# design.net
KiCad netlist of a schematic drawn in EasyEDA Pro
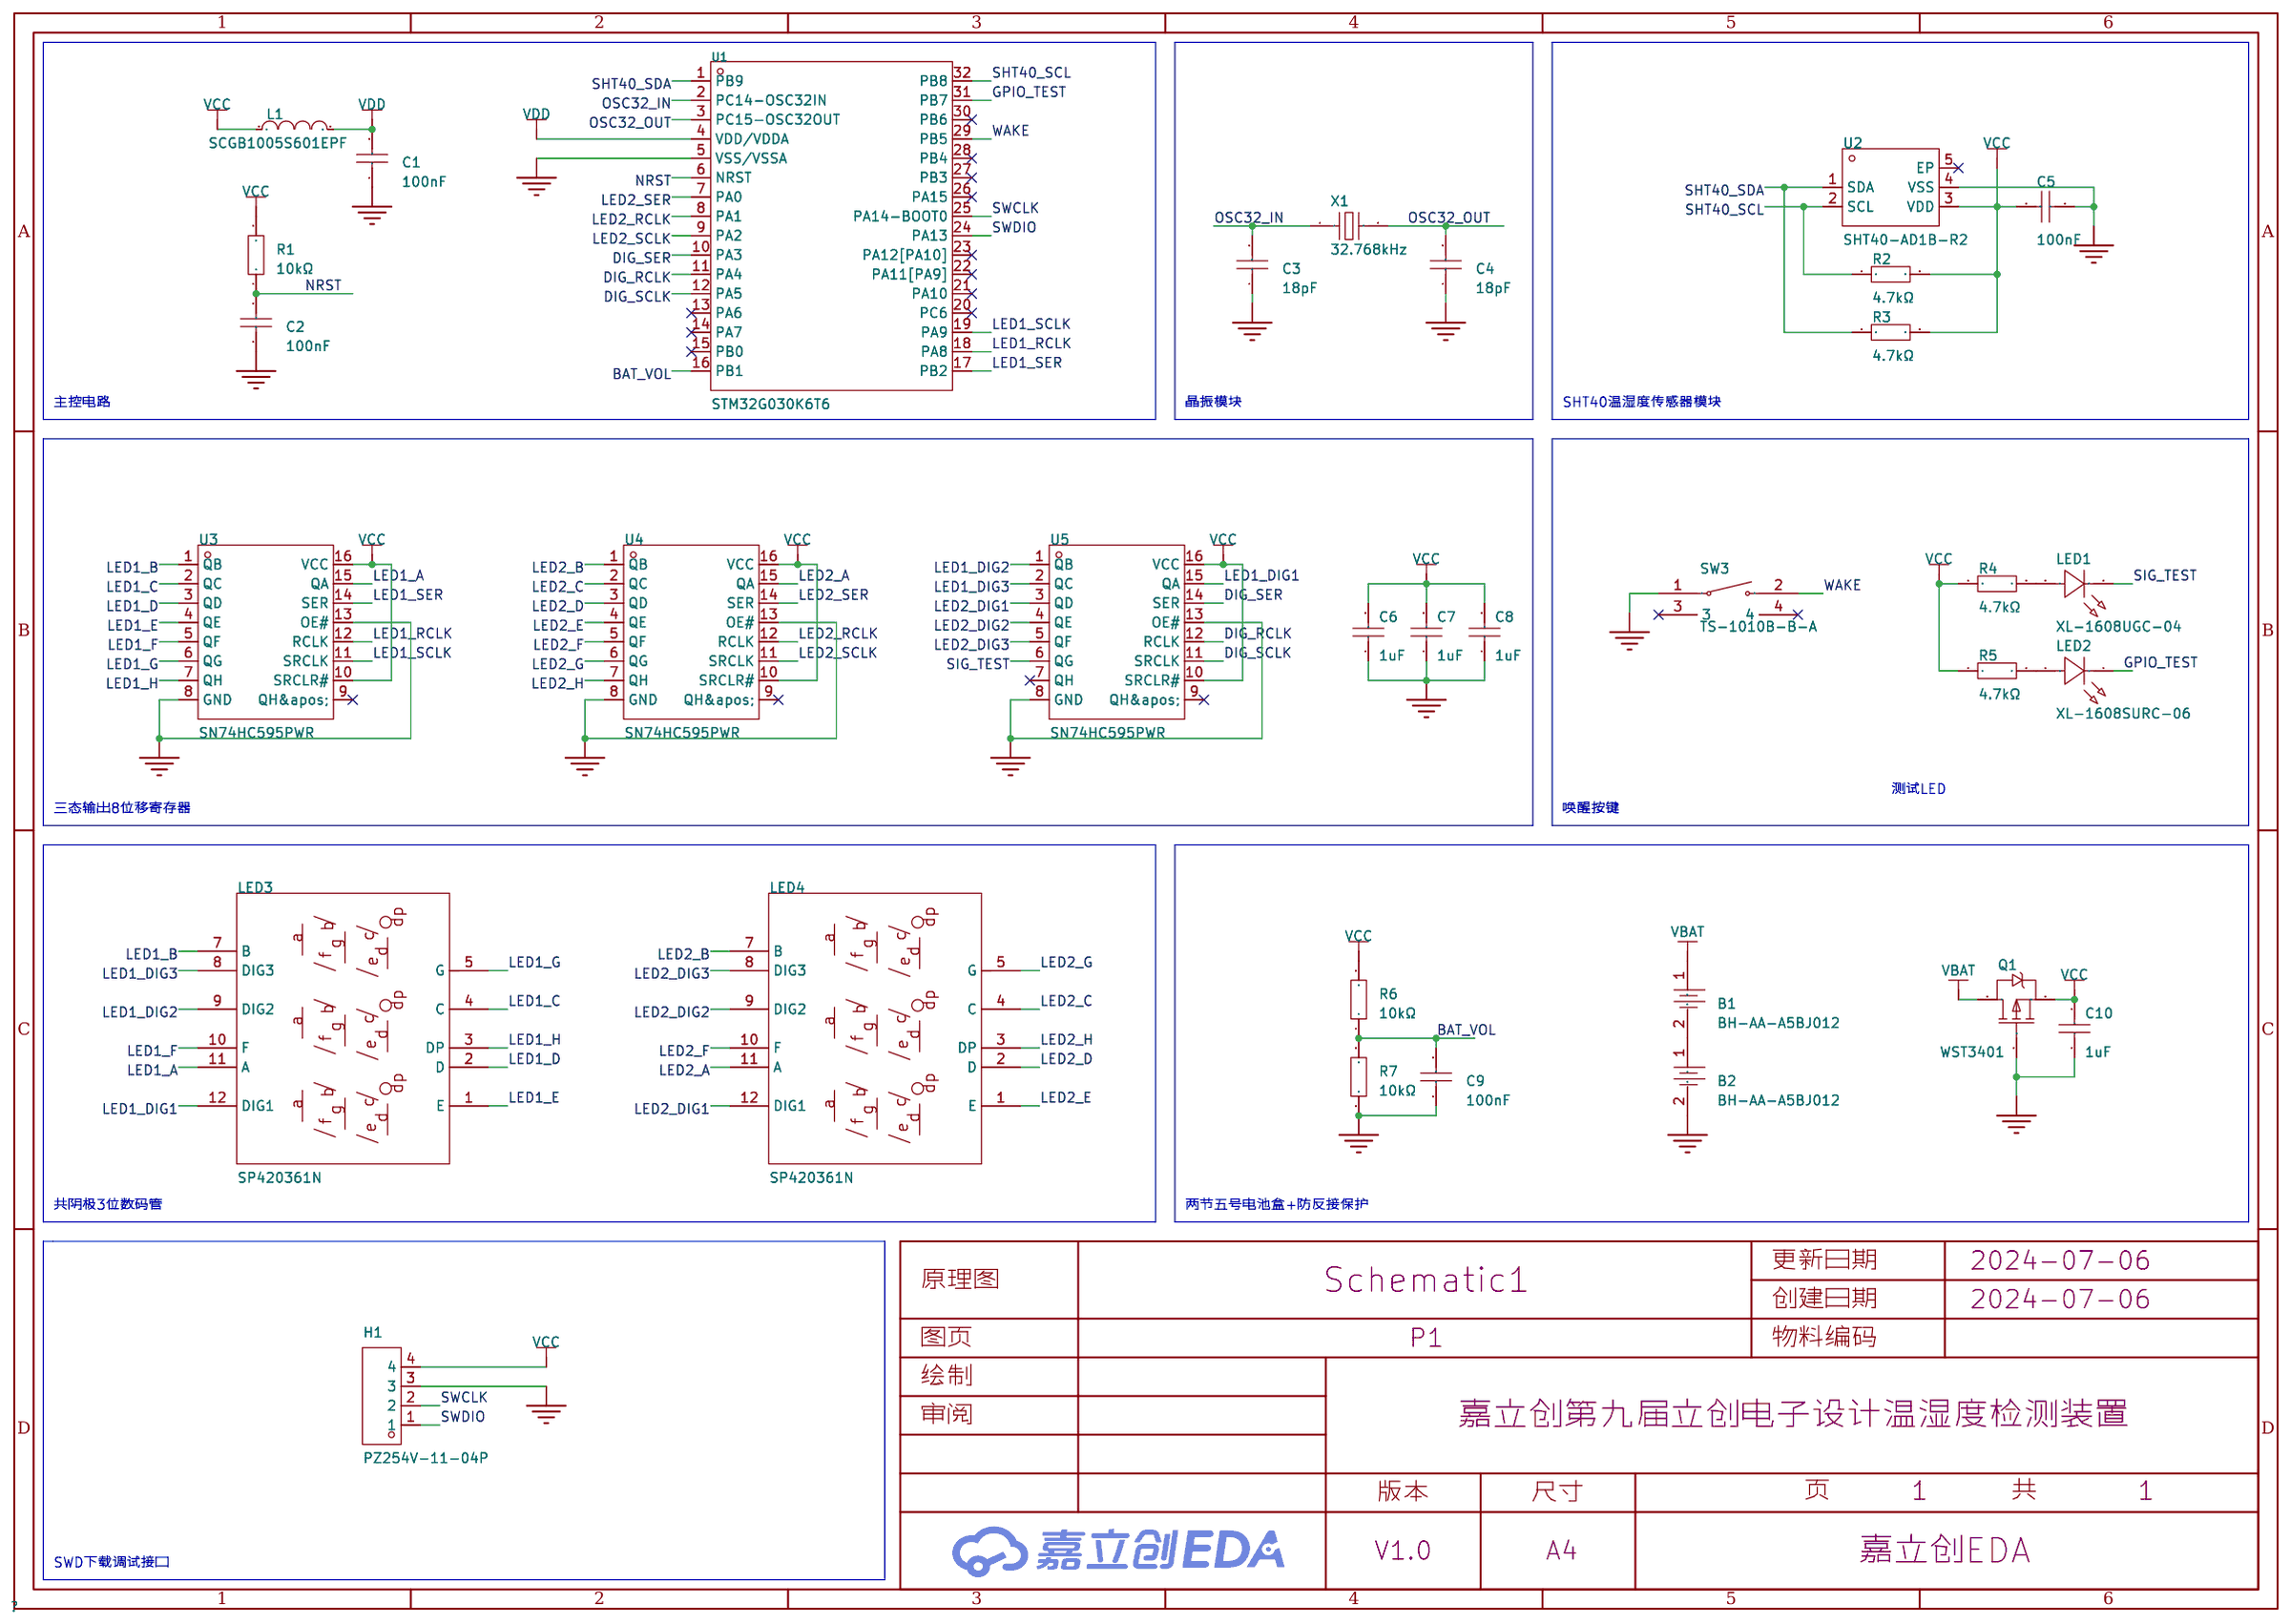
[diagram p0: schematic sheet]

(export (version "E")
  (design (tool "Eeschema 10.0.6"))
  (components
    (comp (ref "B1")
      (value "BH-AA-A5BJ012")
      (footprint "easyedapro:BAT-TH_BH-AA-A5BJ012")
      (description "连接器类型:电池盒;适用电池规格:5号;")
      (fields (field (name "Manufacturer") "MYOUNG(美阳)"))
      (libsource (lib "easyedapro") (part "BH-AA-A5BJ012"))
    )
    (comp (ref "B2")
      (value "BH-AA-A5BJ012")
      (footprint "easyedapro:BAT-TH_BH-AA-A5BJ012")
      (description "连接器类型:电池盒;适用电池规格:5号;")
      (fields (field (name "Manufacturer") "MYOUNG(美阳)"))
      (libsource (lib "easyedapro") (part "BH-AA-A5BJ012"))
    )
    (comp (ref "C1")
      (value "100nF")
      (footprint "easyedapro:C0402")
      (description "容值:100nF;精度:±10%;额定电压:25V;材质(温度系数):X7R;")
      (fields (field (name "Manufacturer Part") "0402B104K250NT") (field (name "Manufacturer") "FH(风华)"))
      (libsource (lib "easyedapro") (part "0402B104K250NT"))
    )
    (comp (ref "C2")
      (value "100nF")
      (footprint "easyedapro:C0402")
      (description "容值:100nF;精度:±10%;额定电压:25V;材质(温度系数):X7R;")
      (fields (field (name "Manufacturer Part") "0402B104K250NT") (field (name "Manufacturer") "FH(风华)"))
      (libsource (lib "easyedapro") (part "0402B104K250NT"))
    )
    (comp (ref "C3")
      (value "18pF")
      (footprint "easyedapro:C0402")
      (description "容值:18pF;精度:±5%;额定电压:50V;材质(温度系数):C0G;")
      (fields (field (name "Manufacturer Part") "0402CG180J500NT") (field (name "Manufacturer") "FH(风华)"))
      (libsource (lib "easyedapro") (part "0402CG180J500NT"))
    )
    (comp (ref "C4")
      (value "18pF")
      (footprint "easyedapro:C0402")
      (description "容值:18pF;精度:±5%;额定电压:50V;材质(温度系数):C0G;")
      (fields (field (name "Manufacturer Part") "0402CG180J500NT") (field (name "Manufacturer") "FH(风华)"))
      (libsource (lib "easyedapro") (part "0402CG180J500NT"))
    )
    (comp (ref "C5")
      (value "100nF")
      (footprint "easyedapro:C0402")
      (description "容值:100nF;精度:±10%;额定电压:25V;材质(温度系数):X7R;")
      (fields (field (name "Manufacturer Part") "0402B104K250NT") (field (name "Manufacturer") "FH(风华)"))
      (libsource (lib "easyedapro") (part "0402B104K250NT"))
    )
    (comp (ref "C6")
      (value "1uF")
      (footprint "easyedapro:C0402")
      (description "容值:1uF;精度:±10%;额定电压:6.3V;材质(温度系数):X5R;")
      (fields (field (name "Manufacturer Part") "0402X105K6R3NT") (field (name "Manufacturer") "FH(风华)"))
      (libsource (lib "easyedapro") (part "0402X105K6R3NT"))
    )
    (comp (ref "C7")
      (value "1uF")
      (footprint "easyedapro:C0402")
      (description "容值:1uF;精度:±10%;额定电压:6.3V;材质(温度系数):X5R;")
      (fields (field (name "Manufacturer Part") "0402X105K6R3NT") (field (name "Manufacturer") "FH(风华)"))
      (libsource (lib "easyedapro") (part "0402X105K6R3NT"))
    )
    (comp (ref "C8")
      (value "1uF")
      (footprint "easyedapro:C0402")
      (description "容值:1uF;精度:±10%;额定电压:6.3V;材质(温度系数):X5R;")
      (fields (field (name "Manufacturer Part") "0402X105K6R3NT") (field (name "Manufacturer") "FH(风华)"))
      (libsource (lib "easyedapro") (part "0402X105K6R3NT"))
    )
    (comp (ref "C9")
      (value "100nF")
      (footprint "easyedapro:C0402")
      (description "容值:100nF;精度:±10%;额定电压:25V;材质(温度系数):X7R;")
      (fields (field (name "Manufacturer Part") "0402B104K250NT") (field (name "Manufacturer") "FH(风华)"))
      (libsource (lib "easyedapro") (part "0402B104K250NT"))
    )
    (comp (ref "C10")
      (value "1uF")
      (footprint "easyedapro:C0402")
      (description "容值:1uF;精度:±10%;额定电压:6.3V;材质(温度系数):X5R;")
      (fields (field (name "Manufacturer Part") "0402X105K6R3NT") (field (name "Manufacturer") "FH(风华)"))
      (libsource (lib "easyedapro") (part "0402X105K6R3NT"))
    )
    (comp (ref "H1")
      (value "PZ254V-11-04P")
      (footprint "easyedapro:HDR-TH_4P-P2.54-V-M")
      (fields (field (name "Manufacturer") "XFCN(兴飞)"))
      (libsource (lib "easyedapro") (part "PZ254V-11-04P_C2691448"))
    )
    (comp (ref "L1")
      (value "SCGB1005S601EPF")
      (footprint "easyedapro:L0402")
      (description "标称阻抗@测试频率:600Ω@100MHz;直流电阻(RDC):1Ω;")
      (fields (field (name "Manufacturer") "SOCAY(硕凯)"))
      (libsource (lib "easyedapro") (part "SCGB1005S601EPF"))
    )
    (comp (ref "LED1")
      (value "XL-1608UGC-04")
      (footprint "easyedapro:LED0603-RD_GREEN")
      (fields (field (name "Manufacturer") "XINGLIGHT(成兴光)"))
      (libsource (lib "easyedapro") (part "XL-1608UGC-04"))
    )
    (comp (ref "LED2")
      (value "XL-1608SURC-06")
      (footprint "easyedapro:LED0603-RD_RED")
      (description "发光颜色:红色;功率:55mW;正向电流:25mA;主波长:617nm~621nm;透镜颜色:无色透明透镜;色温:-;发光角度:120°;载带方式:正贴;工作温度:-30°C~+85°C;")
      (fields (field (name "Manufacturer") "XINGLIGHT(成兴光)"))
      (libsource (lib "easyedapro") (part "XL-1608SURC-06"))
    )
    (comp (ref "LED3")
      (value "SP420361N")
      (footprint "easyedapro:LED-SEG-TH_SP420361N")
      (description "数码管位数:3位;发光颜色:红色;LED极性:共阴极;数字/字母大小(英寸):0.36;")
      (fields (field (name "Manufacturer") "ARKLED(方舟)"))
      (libsource (lib "easyedapro") (part "SP420361N"))
    )
    (comp (ref "LED4")
      (value "SP420361N")
      (footprint "easyedapro:LED-SEG-TH_SP420361N")
      (description "数码管位数:3位;发光颜色:红色;LED极性:共阴极;数字/字母大小(英寸):0.36;")
      (fields (field (name "Manufacturer") "ARKLED(方舟)"))
      (libsource (lib "easyedapro") (part "SP420361N"))
    )
    (comp (ref "Q1")
      (value "WST3401")
      (footprint "easyedapro:SOT-23-3_L2.9-W1.6-P1.90-LS2.8-BR")
      (fields (field (name "Manufacturer") "WINSOK(微硕)"))
      (libsource (lib "easyedapro") (part "WST3401"))
    )
    (comp (ref "R1")
      (value "10kΩ")
      (footprint "easyedapro:R0402")
      (description "电阻类型:厚膜电阻;阻值:10kΩ;精度:±1%;功率:62.5mW;最大工作电压:50V;温度系数:±100ppm/°C;")
      (fields (field (name "Manufacturer Part") "RC0402FR-0710KL") (field (name "Manufacturer") "YAGEO(国巨)"))
      (libsource (lib "easyedapro") (part "RC0402FR-0710KL"))
    )
    (comp (ref "R2")
      (value "4.7kΩ")
      (footprint "easyedapro:R0402")
      (description "电阻类型:厚膜电阻;阻值:4.7kΩ;精度:±1%;功率:62.5mW;最大工作电压:50V;温度系数:±100ppm/°C;")
      (fields (field (name "Manufacturer Part") "RC0402FR-074K7L") (field (name "Manufacturer") "YAGEO(国巨)"))
      (libsource (lib "easyedapro") (part "RC0402FR-074K7L"))
    )
    (comp (ref "R3")
      (value "4.7kΩ")
      (footprint "easyedapro:R0402")
      (description "电阻类型:厚膜电阻;阻值:4.7kΩ;精度:±1%;功率:62.5mW;最大工作电压:50V;温度系数:±100ppm/°C;")
      (fields (field (name "Manufacturer Part") "RC0402FR-074K7L") (field (name "Manufacturer") "YAGEO(国巨)"))
      (libsource (lib "easyedapro") (part "RC0402FR-074K7L"))
    )
    (comp (ref "R4")
      (value "4.7kΩ")
      (footprint "easyedapro:R0402")
      (description "电阻类型:厚膜电阻;阻值:4.7kΩ;精度:±1%;功率:62.5mW;最大工作电压:50V;温度系数:±100ppm/°C;")
      (fields (field (name "Manufacturer Part") "RC0402FR-074K7L") (field (name "Manufacturer") "YAGEO(国巨)"))
      (libsource (lib "easyedapro") (part "RC0402FR-074K7L"))
    )
    (comp (ref "R5")
      (value "4.7kΩ")
      (footprint "easyedapro:R0402")
      (description "电阻类型:厚膜电阻;阻值:4.7kΩ;精度:±1%;功率:62.5mW;最大工作电压:50V;温度系数:±100ppm/°C;")
      (fields (field (name "Manufacturer Part") "RC0402FR-074K7L") (field (name "Manufacturer") "YAGEO(国巨)"))
      (libsource (lib "easyedapro") (part "RC0402FR-074K7L"))
    )
    (comp (ref "R6")
      (value "10kΩ")
      (footprint "easyedapro:R0402")
      (description "电阻类型:厚膜电阻;阻值:10kΩ;精度:±1%;功率:62.5mW;最大工作电压:50V;温度系数:±100ppm/°C;")
      (fields (field (name "Manufacturer Part") "RC0402FR-0710KL") (field (name "Manufacturer") "YAGEO(国巨)"))
      (libsource (lib "easyedapro") (part "RC0402FR-0710KL"))
    )
    (comp (ref "R7")
      (value "10kΩ")
      (footprint "easyedapro:R0402")
      (description "电阻类型:厚膜电阻;阻值:10kΩ;精度:±1%;功率:62.5mW;最大工作电压:50V;温度系数:±100ppm/°C;")
      (fields (field (name "Manufacturer Part") "RC0402FR-0710KL") (field (name "Manufacturer") "YAGEO(国巨)"))
      (libsource (lib "easyedapro") (part "RC0402FR-0710KL"))
    )
    (comp (ref "SW3")
      (value "TS-1010B-B-A")
      (footprint "easyedapro:SW-SMD_TS-1010B-B-A")
      (fields (field (name "Manufacturer") "XKB Connectivity(中国星坤)"))
      (libsource (lib "easyedapro") (part "TS-1010B-B-A"))
    )
    (comp (ref "U1")
      (value "STM32G030K6T6")
      (footprint "easyedapro:LQFP-32_L7.0-W7.0-P0.80-LS9.0-BL")
      (description "CPU内核:CM0;程序存储容量:32KB;RAM总容量:8KB;GPIO端口数量:30;工作电压范围:2V~3.6V;CPU最大主频:64MHz;程序存储器类型:FLASH;")
      (fields (field (name "Manufacturer") "ST(意法半导体)"))
      (libsource (lib "easyedapro") (part "STM32G030K6T6"))
    )
    (comp (ref "U2")
      (value "SHT40-AD1B-R2")
      (footprint "easyedapro:DFN-4_L1.5-W1.5-P0.8-TL-EP")
      (description "±1.8% / max. ±3.5% RH 数字温湿度传感器")
      (fields (field (name "Manufacturer") "Sensirion(瑞士盛思锐)"))
      (libsource (lib "easyedapro") (part "SHT40-AD1B-R2"))
    )
    (comp (ref "U3")
      (value "SN74HC595PWR")
      (footprint "easyedapro:TSSOP-16_L5.0-W4.4-P0.65-LS6.4-BL")
      (description "功能:串行至串行或并行;电源电压:2V~6V;元件数:1;每个元件位数:8;")
      (fields (field (name "Manufacturer") "TI(德州仪器)"))
      (libsource (lib "easyedapro") (part "SN74HC595PWR"))
    )
    (comp (ref "U4")
      (value "SN74HC595PWR")
      (footprint "easyedapro:TSSOP-16_L5.0-W4.4-P0.65-LS6.4-BL")
      (description "功能:串行至串行或并行;电源电压:2V~6V;元件数:1;每个元件位数:8;")
      (fields (field (name "Manufacturer") "TI(德州仪器)"))
      (libsource (lib "easyedapro") (part "SN74HC595PWR"))
    )
    (comp (ref "U5")
      (value "SN74HC595PWR")
      (footprint "easyedapro:TSSOP-16_L5.0-W4.4-P0.65-LS6.4-BL")
      (description "功能:串行至串行或并行;电源电压:2V~6V;元件数:1;每个元件位数:8;")
      (fields (field (name "Manufacturer") "TI(德州仪器)"))
      (libsource (lib "easyedapro") (part "SN74HC595PWR"))
    )
    (comp (ref "X1")
      (value "32.768kHz")
      (footprint "easyedapro:OSC-SMD_L3.2-W1.5")
      (description "晶振类型:贴片晶振;频率:32.768kHz;常温频差:±20ppm;外接负载电容:12.5pF;频率稳定度(全温):-;")
      (fields (field (name "Manufacturer Part") "X321532768KGD2SI") (field (name "Manufacturer") "YXC(扬兴晶振)"))
      (libsource (lib "easyedapro") (part "X321532768KGD2SI"))
    )
  )
  (nets
    (net (code "1") (name "/BAT_VOL") (class "Default")
      (node (ref "C9") (pin "1") (pinfunction "1_1") (pintype "input"))
      (node (ref "R6") (pin "1") (pinfunction "1_1") (pintype "input"))
      (node (ref "R7") (pin "2") (pinfunction "2_2") (pintype "input"))
      (node (ref "U1") (pin "16") (pinfunction "PB1_16") (pintype "input"))
    )
    (net (code "2") (name "/DIG_RCLK") (class "Default")
      (node (ref "U1") (pin "11") (pinfunction "PA4_11") (pintype "input"))
      (node (ref "U5") (pin "12") (pinfunction "RCLK_12") (pintype "unspecified"))
    )
    (net (code "3") (name "/DIG_SCLK") (class "Default")
      (node (ref "U1") (pin "12") (pinfunction "PA5_12") (pintype "input"))
      (node (ref "U5") (pin "11") (pinfunction "SRCLK_11") (pintype "unspecified"))
    )
    (net (code "4") (name "/DIG_SER") (class "Default")
      (node (ref "U1") (pin "10") (pinfunction "PA3_10") (pintype "input"))
      (node (ref "U5") (pin "14") (pinfunction "SER_14") (pintype "unspecified"))
    )
    (net (code "5") (name "/GPIO_TEST") (class "Default")
      (node (ref "LED2") (pin "1") (pinfunction "K_1") (pintype "unspecified"))
      (node (ref "U1") (pin "31") (pinfunction "PB7_31") (pintype "input"))
    )
    (net (code "6") (name "/LED1_A") (class "Default")
      (node (ref "LED3") (pin "11") (pinfunction "A_11") (pintype "input"))
      (node (ref "U3") (pin "15") (pinfunction "QA_15") (pintype "unspecified"))
    )
    (net (code "7") (name "/LED1_B") (class "Default")
      (node (ref "LED3") (pin "7") (pinfunction "B_7") (pintype "input"))
      (node (ref "U3") (pin "1") (pinfunction "QB_1") (pintype "unspecified"))
    )
    (net (code "8") (name "/LED1_C") (class "Default")
      (node (ref "LED3") (pin "4") (pinfunction "C_4") (pintype "input"))
      (node (ref "U3") (pin "2") (pinfunction "QC_2") (pintype "unspecified"))
    )
    (net (code "9") (name "/LED1_D") (class "Default")
      (node (ref "LED3") (pin "2") (pinfunction "D_2") (pintype "input"))
      (node (ref "U3") (pin "3") (pinfunction "QD_3") (pintype "unspecified"))
    )
    (net (code "10") (name "/LED1_DIG1") (class "Default")
      (node (ref "LED3") (pin "12") (pinfunction "DIG1_12") (pintype "input"))
      (node (ref "U5") (pin "15") (pinfunction "QA_15") (pintype "unspecified"))
    )
    (net (code "11") (name "/LED1_DIG2") (class "Default")
      (node (ref "LED3") (pin "9") (pinfunction "DIG2_9") (pintype "input"))
      (node (ref "U5") (pin "1") (pinfunction "QB_1") (pintype "unspecified"))
    )
    (net (code "12") (name "/LED1_DIG3") (class "Default")
      (node (ref "LED3") (pin "8") (pinfunction "DIG3_8") (pintype "input"))
      (node (ref "U5") (pin "2") (pinfunction "QC_2") (pintype "unspecified"))
    )
    (net (code "13") (name "/LED1_E") (class "Default")
      (node (ref "LED3") (pin "1") (pinfunction "E_1") (pintype "input"))
      (node (ref "U3") (pin "4") (pinfunction "QE_4") (pintype "unspecified"))
    )
    (net (code "14") (name "/LED1_F") (class "Default")
      (node (ref "LED3") (pin "10") (pinfunction "F_10") (pintype "input"))
      (node (ref "U3") (pin "5") (pinfunction "QF_5") (pintype "unspecified"))
    )
    (net (code "15") (name "/LED1_G") (class "Default")
      (node (ref "LED3") (pin "5") (pinfunction "G_5") (pintype "input"))
      (node (ref "U3") (pin "6") (pinfunction "QG_6") (pintype "unspecified"))
    )
    (net (code "16") (name "/LED1_H") (class "Default")
      (node (ref "LED3") (pin "3") (pinfunction "DP_3") (pintype "input"))
      (node (ref "U3") (pin "7") (pinfunction "QH_7") (pintype "unspecified"))
    )
    (net (code "17") (name "/LED1_RCLK") (class "Default")
      (node (ref "U1") (pin "18") (pinfunction "PA8_18") (pintype "input"))
      (node (ref "U3") (pin "12") (pinfunction "RCLK_12") (pintype "unspecified"))
    )
    (net (code "18") (name "/LED1_SCLK") (class "Default")
      (node (ref "U1") (pin "19") (pinfunction "PA9_19") (pintype "input"))
      (node (ref "U3") (pin "11") (pinfunction "SRCLK_11") (pintype "unspecified"))
    )
    (net (code "19") (name "/LED1_SER") (class "Default")
      (node (ref "U1") (pin "17") (pinfunction "PB2_17") (pintype "input"))
      (node (ref "U3") (pin "14") (pinfunction "SER_14") (pintype "unspecified"))
    )
    (net (code "20") (name "/LED2_A") (class "Default")
      (node (ref "LED4") (pin "11") (pinfunction "A_11") (pintype "input"))
      (node (ref "U4") (pin "15") (pinfunction "QA_15") (pintype "unspecified"))
    )
    (net (code "21") (name "/LED2_B") (class "Default")
      (node (ref "LED4") (pin "7") (pinfunction "B_7") (pintype "input"))
      (node (ref "U4") (pin "1") (pinfunction "QB_1") (pintype "unspecified"))
    )
    (net (code "22") (name "/LED2_C") (class "Default")
      (node (ref "LED4") (pin "4") (pinfunction "C_4") (pintype "input"))
      (node (ref "U4") (pin "2") (pinfunction "QC_2") (pintype "unspecified"))
    )
    (net (code "23") (name "/LED2_D") (class "Default")
      (node (ref "LED4") (pin "2") (pinfunction "D_2") (pintype "input"))
      (node (ref "U4") (pin "3") (pinfunction "QD_3") (pintype "unspecified"))
    )
    (net (code "24") (name "/LED2_DIG1") (class "Default")
      (node (ref "LED4") (pin "12") (pinfunction "DIG1_12") (pintype "input"))
      (node (ref "U5") (pin "3") (pinfunction "QD_3") (pintype "unspecified"))
    )
    (net (code "25") (name "/LED2_DIG2") (class "Default")
      (node (ref "LED4") (pin "9") (pinfunction "DIG2_9") (pintype "input"))
      (node (ref "U5") (pin "4") (pinfunction "QE_4") (pintype "unspecified"))
    )
    (net (code "26") (name "/LED2_DIG3") (class "Default")
      (node (ref "LED4") (pin "8") (pinfunction "DIG3_8") (pintype "input"))
      (node (ref "U5") (pin "5") (pinfunction "QF_5") (pintype "unspecified"))
    )
    (net (code "27") (name "/LED2_E") (class "Default")
      (node (ref "LED4") (pin "1") (pinfunction "E_1") (pintype "input"))
      (node (ref "U4") (pin "4") (pinfunction "QE_4") (pintype "unspecified"))
    )
    (net (code "28") (name "/LED2_F") (class "Default")
      (node (ref "LED4") (pin "10") (pinfunction "F_10") (pintype "input"))
      (node (ref "U4") (pin "5") (pinfunction "QF_5") (pintype "unspecified"))
    )
    (net (code "29") (name "/LED2_G") (class "Default")
      (node (ref "LED4") (pin "5") (pinfunction "G_5") (pintype "input"))
      (node (ref "U4") (pin "6") (pinfunction "QG_6") (pintype "unspecified"))
    )
    (net (code "30") (name "/LED2_H") (class "Default")
      (node (ref "LED4") (pin "3") (pinfunction "DP_3") (pintype "input"))
      (node (ref "U4") (pin "7") (pinfunction "QH_7") (pintype "unspecified"))
    )
    (net (code "31") (name "/LED2_RCLK") (class "Default")
      (node (ref "U1") (pin "8") (pinfunction "PA1_8") (pintype "input"))
      (node (ref "U4") (pin "12") (pinfunction "RCLK_12") (pintype "unspecified"))
    )
    (net (code "32") (name "/LED2_SCLK") (class "Default")
      (node (ref "U1") (pin "9") (pinfunction "PA2_9") (pintype "input"))
      (node (ref "U4") (pin "11") (pinfunction "SRCLK_11") (pintype "unspecified"))
    )
    (net (code "33") (name "/LED2_SER") (class "Default")
      (node (ref "U1") (pin "7") (pinfunction "PA0_7") (pintype "input"))
      (node (ref "U4") (pin "14") (pinfunction "SER_14") (pintype "unspecified"))
    )
    (net (code "34") (name "/NRST") (class "Default")
      (node (ref "C2") (pin "1") (pinfunction "1_1") (pintype "input"))
      (node (ref "R1") (pin "1") (pinfunction "1_1") (pintype "input"))
      (node (ref "U1") (pin "6") (pinfunction "NRST_6") (pintype "input"))
    )
    (net (code "35") (name "/OSC32_IN") (class "Default")
      (node (ref "C3") (pin "2") (pinfunction "2_2") (pintype "input"))
      (node (ref "U1") (pin "2") (pinfunction "PC14-OSC32IN_2") (pintype "input"))
      (node (ref "X1") (pin "1") (pinfunction "1_1") (pintype "input"))
    )
    (net (code "36") (name "/OSC32_OUT") (class "Default")
      (node (ref "C4") (pin "2") (pinfunction "2_2") (pintype "input"))
      (node (ref "U1") (pin "3") (pinfunction "PC15-OSC32OUT_3") (pintype "input"))
      (node (ref "X1") (pin "2") (pinfunction "2_2") (pintype "input"))
    )
    (net (code "37") (name "/SHT40_SCL") (class "Default")
      (node (ref "R2") (pin "1") (pinfunction "1_1") (pintype "input"))
      (node (ref "U1") (pin "32") (pinfunction "PB8_32") (pintype "input"))
      (node (ref "U2") (pin "2") (pinfunction "SCL_2") (pintype "unspecified"))
    )
    (net (code "38") (name "/SHT40_SDA") (class "Default")
      (node (ref "R3") (pin "1") (pinfunction "1_1") (pintype "input"))
      (node (ref "U1") (pin "1") (pinfunction "PB9_1") (pintype "input"))
      (node (ref "U2") (pin "1") (pinfunction "SDA_1") (pintype "unspecified"))
    )
    (net (code "39") (name "/SIG_TEST") (class "Default")
      (node (ref "LED1") (pin "1") (pinfunction "K_1") (pintype "unspecified"))
      (node (ref "U5") (pin "6") (pinfunction "QG_6") (pintype "unspecified"))
    )
    (net (code "40") (name "/SWCLK") (class "Default")
      (node (ref "H1") (pin "2") (pinfunction "2_2") (pintype "unspecified"))
      (node (ref "U1") (pin "25") (pinfunction "PA14-BOOT0_25") (pintype "input"))
    )
    (net (code "41") (name "/SWDIO") (class "Default")
      (node (ref "H1") (pin "1") (pinfunction "1_1") (pintype "unspecified"))
      (node (ref "U1") (pin "24") (pinfunction "PA13_24") (pintype "input"))
    )
    (net (code "42") (name "/WAKE") (class "Default")
      (node (ref "SW3") (pin "2") (pinfunction "2_2") (pintype "input"))
      (node (ref "U1") (pin "29") (pinfunction "PB5_29") (pintype "input"))
    )
    (net (code "43") (name "GND") (class "Default")
      (node (ref "B2") (pin "2") (pinfunction "2_2") (pintype "input"))
      (node (ref "C1") (pin "2") (pinfunction "2_2") (pintype "input"))
      (node (ref "C10") (pin "1") (pinfunction "1_1") (pintype "input"))
      (node (ref "C2") (pin "2") (pinfunction "2_2") (pintype "input"))
      (node (ref "C3") (pin "1") (pinfunction "1_1") (pintype "input"))
      (node (ref "C4") (pin "1") (pinfunction "1_1") (pintype "input"))
      (node (ref "C5") (pin "2") (pinfunction "2_2") (pintype "input"))
      (node (ref "C6") (pin "1") (pinfunction "1_1") (pintype "input"))
      (node (ref "C7") (pin "1") (pinfunction "1_1") (pintype "input"))
      (node (ref "C8") (pin "1") (pinfunction "1_1") (pintype "input"))
      (node (ref "C9") (pin "2") (pinfunction "2_2") (pintype "input"))
      (node (ref "H1") (pin "3") (pinfunction "3_3") (pintype "unspecified"))
      (node (ref "Q1") (pin "1") (pinfunction "G_1") (pintype "unspecified"))
      (node (ref "R7") (pin "1") (pinfunction "1_1") (pintype "input"))
      (node (ref "SW3") (pin "1") (pinfunction "1_1") (pintype "input"))
      (node (ref "U1") (pin "5") (pinfunction "VSS/VSSA_5") (pintype "input"))
      (node (ref "U2") (pin "4") (pinfunction "VSS_4") (pintype "unspecified"))
      (node (ref "U3") (pin "13") (pinfunction "OE#_13") (pintype "unspecified"))
      (node (ref "U3") (pin "8") (pinfunction "GND_8") (pintype "unspecified"))
      (node (ref "U4") (pin "13") (pinfunction "OE#_13") (pintype "unspecified"))
      (node (ref "U4") (pin "8") (pinfunction "GND_8") (pintype "unspecified"))
      (node (ref "U5") (pin "13") (pinfunction "OE#_13") (pintype "unspecified"))
      (node (ref "U5") (pin "8") (pinfunction "GND_8") (pintype "unspecified"))
    )
    (net (code "44") (name "Net-(B1-Pad2)") (class "Default")
      (node (ref "B1") (pin "2") (pinfunction "2_2") (pintype "input"))
      (node (ref "B2") (pin "1") (pinfunction "1_1") (pintype "input"))
    )
    (net (code "45") (name "Net-(LED1-A)") (class "Default")
      (node (ref "LED1") (pin "2") (pinfunction "A_2") (pintype "unspecified"))
      (node (ref "R4") (pin "2") (pinfunction "2_2") (pintype "input"))
    )
    (net (code "46") (name "Net-(LED2-A)") (class "Default")
      (node (ref "LED2") (pin "2") (pinfunction "A_2") (pintype "unspecified"))
      (node (ref "R5") (pin "2") (pinfunction "2_2") (pintype "input"))
    )
    (net (code "47") (name "VBAT") (class "Default")
      (node (ref "B1") (pin "1") (pinfunction "1_1") (pintype "input"))
      (node (ref "Q1") (pin "3") (pinfunction "D_3") (pintype "unspecified"))
    )
    (net (code "48") (name "VCC") (class "Default")
      (node (ref "C10") (pin "2") (pinfunction "2_2") (pintype "input"))
      (node (ref "C5") (pin "1") (pinfunction "1_1") (pintype "input"))
      (node (ref "C6") (pin "2") (pinfunction "2_2") (pintype "input"))
      (node (ref "C7") (pin "2") (pinfunction "2_2") (pintype "input"))
      (node (ref "C8") (pin "2") (pinfunction "2_2") (pintype "input"))
      (node (ref "H1") (pin "4") (pinfunction "4_4") (pintype "unspecified"))
      (node (ref "L1") (pin "1") (pinfunction "1_1") (pintype "unspecified"))
      (node (ref "Q1") (pin "2") (pinfunction "S_2") (pintype "unspecified"))
      (node (ref "R1") (pin "2") (pinfunction "2_2") (pintype "input"))
      (node (ref "R2") (pin "2") (pinfunction "2_2") (pintype "input"))
      (node (ref "R3") (pin "2") (pinfunction "2_2") (pintype "input"))
      (node (ref "R4") (pin "1") (pinfunction "1_1") (pintype "input"))
      (node (ref "R5") (pin "1") (pinfunction "1_1") (pintype "input"))
      (node (ref "R6") (pin "2") (pinfunction "2_2") (pintype "input"))
      (node (ref "U2") (pin "3") (pinfunction "VDD_3") (pintype "unspecified"))
      (node (ref "U3") (pin "10") (pinfunction "SRCLR#_10") (pintype "unspecified"))
      (node (ref "U3") (pin "16") (pinfunction "VCC_16") (pintype "unspecified"))
      (node (ref "U4") (pin "10") (pinfunction "SRCLR#_10") (pintype "unspecified"))
      (node (ref "U4") (pin "16") (pinfunction "VCC_16") (pintype "unspecified"))
      (node (ref "U5") (pin "10") (pinfunction "SRCLR#_10") (pintype "unspecified"))
      (node (ref "U5") (pin "16") (pinfunction "VCC_16") (pintype "unspecified"))
    )
    (net (code "49") (name "VDD") (class "Default")
      (node (ref "C1") (pin "1") (pinfunction "1_1") (pintype "input"))
      (node (ref "L1") (pin "2") (pinfunction "2_2") (pintype "unspecified"))
      (node (ref "U1") (pin "4") (pinfunction "VDD/VDDA_4") (pintype "input"))
    )
    (net (code "50") (name "unconnected-(SW3-Pad3)") (class "Default")
      (node (ref "SW3") (pin "3") (pinfunction "3_3") (pintype "input+no_connect"))
    )
    (net (code "51") (name "unconnected-(SW3-Pad4)") (class "Default")
      (node (ref "SW3") (pin "4") (pinfunction "4_4") (pintype "input+no_connect"))
    )
    (net (code "52") (name "unconnected-(U1-PA6-Pad13)") (class "Default")
      (node (ref "U1") (pin "13") (pinfunction "PA6_13") (pintype "input+no_connect"))
    )
    (net (code "53") (name "unconnected-(U1-PA7-Pad14)") (class "Default")
      (node (ref "U1") (pin "14") (pinfunction "PA7_14") (pintype "input+no_connect"))
    )
    (net (code "54") (name "unconnected-(U1-PA10-Pad21)") (class "Default")
      (node (ref "U1") (pin "21") (pinfunction "PA10_21") (pintype "input+no_connect"))
    )
    (net (code "55") (name "unconnected-(U1-PA11[PA9]-Pad22)") (class "Default")
      (node (ref "U1") (pin "22") (pinfunction "PA11[PA9]_22") (pintype "input+no_connect"))
    )
    (net (code "56") (name "unconnected-(U1-PA12[PA10]-Pad23)") (class "Default")
      (node (ref "U1") (pin "23") (pinfunction "PA12[PA10]_23") (pintype "input+no_connect"))
    )
    (net (code "57") (name "unconnected-(U1-PA15-Pad26)") (class "Default")
      (node (ref "U1") (pin "26") (pinfunction "PA15_26") (pintype "input+no_connect"))
    )
    (net (code "58") (name "unconnected-(U1-PB0-Pad15)") (class "Default")
      (node (ref "U1") (pin "15") (pinfunction "PB0_15") (pintype "input+no_connect"))
    )
    (net (code "59") (name "unconnected-(U1-PB3-Pad27)") (class "Default")
      (node (ref "U1") (pin "27") (pinfunction "PB3_27") (pintype "input+no_connect"))
    )
    (net (code "60") (name "unconnected-(U1-PB4-Pad28)") (class "Default")
      (node (ref "U1") (pin "28") (pinfunction "PB4_28") (pintype "input+no_connect"))
    )
    (net (code "61") (name "unconnected-(U1-PB6-Pad30)") (class "Default")
      (node (ref "U1") (pin "30") (pinfunction "PB6_30") (pintype "input+no_connect"))
    )
    (net (code "62") (name "unconnected-(U1-PC6-Pad20)") (class "Default")
      (node (ref "U1") (pin "20") (pinfunction "PC6_20") (pintype "input+no_connect"))
    )
    (net (code "63") (name "unconnected-(U2-EP-Pad5)") (class "Default")
      (node (ref "U2") (pin "5") (pinfunction "EP_5") (pintype "unspecified+no_connect"))
    )
    (net (code "64") (name "unconnected-(U3-QH&apos;-Pad9)") (class "Default")
      (node (ref "U3") (pin "9") (pinfunction "QH&apos;_9") (pintype "unspecified+no_connect"))
    )
    (net (code "65") (name "unconnected-(U4-QH&apos;-Pad9)") (class "Default")
      (node (ref "U4") (pin "9") (pinfunction "QH&apos;_9") (pintype "unspecified+no_connect"))
    )
    (net (code "66") (name "unconnected-(U5-QH&apos;-Pad9)") (class "Default")
      (node (ref "U5") (pin "9") (pinfunction "QH&apos;_9") (pintype "unspecified+no_connect"))
    )
    (net (code "67") (name "unconnected-(U5-QH-Pad7)") (class "Default")
      (node (ref "U5") (pin "7") (pinfunction "QH_7") (pintype "unspecified+no_connect"))
    )
  )
)
